# 5_LCD.net
KiCad netlist of a schematic drawn in Altium Designer
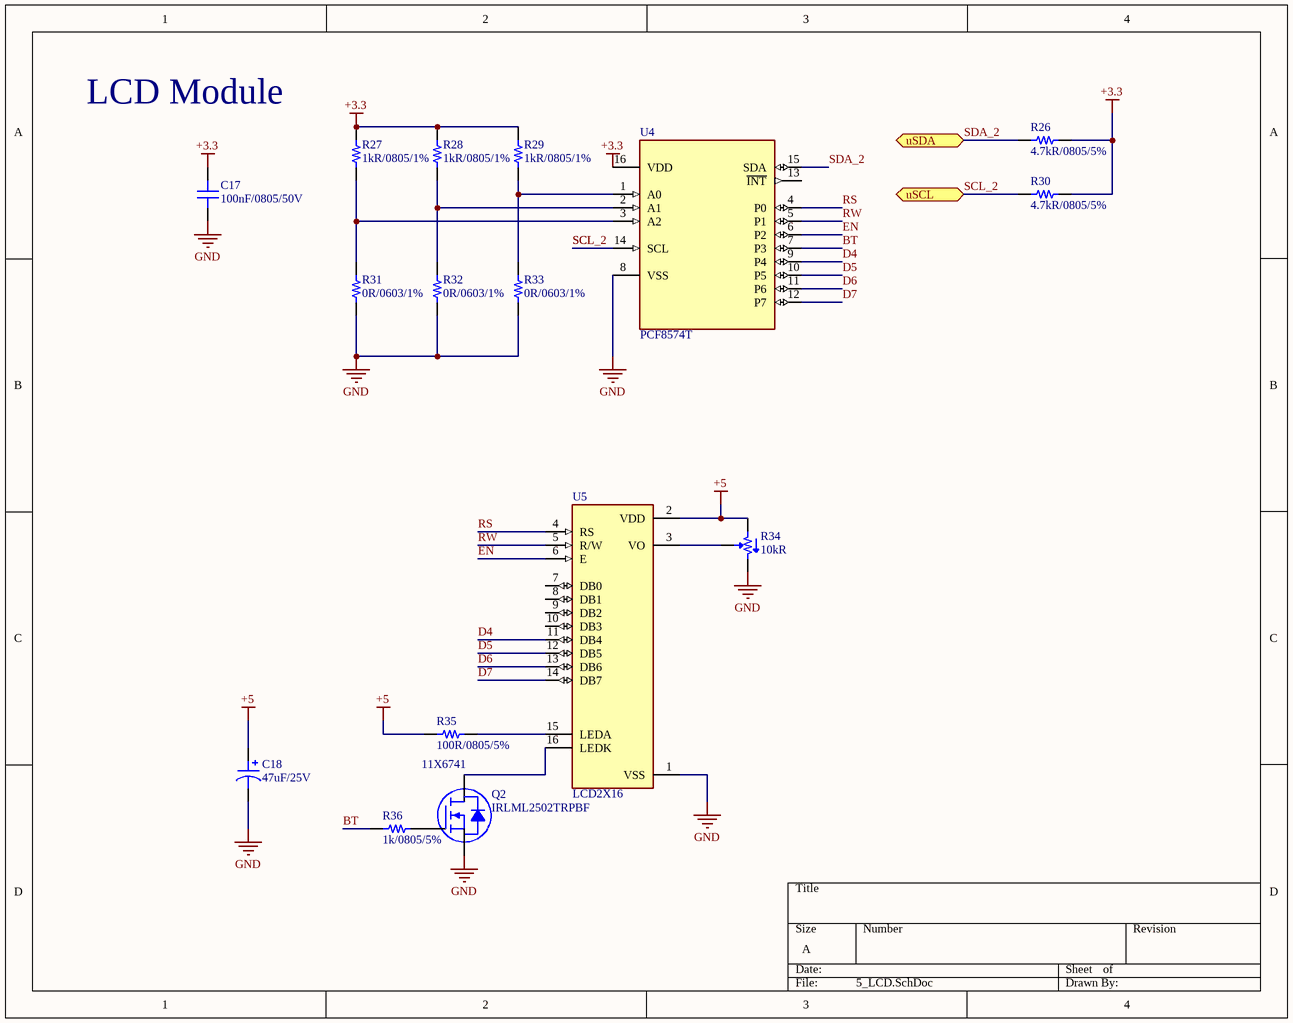
[diagram p0: 5_LCD.SchDoc]

(export (version "E")
  (design (tool "Eeschema 10.0.6"))
  (components
    (comp (ref "C17")
      (value "100nF/0805/50V")
      (footprint "CAP FILM 0805")
      (description "Multilayer Ceramic Capacitor, 0.1 uF, 50 V, ï¿½ 10%, X7R, 0805 [2012 Metric]")
      (fields
        (field (name "MANUFACTURER") "Samsung")
        (field (name "MANUFACTURER PART NUMBER") "CL21B104KBCNNNC")
      )
      (libsource (lib "NLOC_Altium_Library") (part "Capacitor - MLCC"))
    )
    (comp (ref "C18")
      (value "47uF/25V")
      (footprint "CAP ALSMD 6.6MM H5.4MM")
      (description "SMT Polarised Capacitor")
      (libsource (lib "NLOC_Altium_Library") (part "Capacitor - Aluminum"))
    )
    (comp (ref "Q2")
      (value "IRLML2502TRPBF")
      (footprint "TI SOT-23-3 DBZ")
      (description "Mosfet, Power; N-ch; Vdss 20V; Rds(on) 0.035 Ohm; Id 4.2A; MICRO3; Pd 1.25W; Vgs +/-12V")
      (fields
        (field (name "SUPPLIER PART NUMBER 1") "11X6741")
        (field (name "MANUFACTURER") "International Rectifier")
      )
      (libsource (lib "NLOC_Sche") (part "MOSFET N-CH"))
    )
    (comp (ref "R26")
      (value "4.7kR/0805/5%")
      (footprint "RES 0805_2012")
      (description "SMD Chip Resistor, 4.7 kOhm, ± 5%, 125 mW, 0805 [2012 Metric], Thick Film, General Purpose")
      (fields
        (field (name "MANUFACTURER") "Vishay Dale")
        (field (name "MANUFACTURER PART NUMBER") "CRCW08054K70JNEA")
      )
      (libsource (lib "NLOC_Altium_Library") (part "Resistor"))
    )
    (comp (ref "R27")
      (value "1kR/0805/1%")
      (footprint "RES 0805_2012")
      (description "SMD Chip Resistor, 1 kOhm, ï¿½ 1%, 125 mW, 0805 [2012 Metric], Thick Film, General Purpose")
      (fields
        (field (name "MANUFACTURER") "Yageo")
        (field (name "MANUFACTURER PART NUMBER") "RC0805FR-071KL")
      )
      (libsource (lib "NLOC_Altium_Library") (part "Resistor"))
    )
    (comp (ref "R28")
      (value "1kR/0805/1%")
      (footprint "RES 0805_2012")
      (description "SMD Chip Resistor, 1 kOhm, ï¿½ 1%, 125 mW, 0805 [2012 Metric], Thick Film, General Purpose")
      (fields
        (field (name "MANUFACTURER") "Yageo")
        (field (name "MANUFACTURER PART NUMBER") "RC0805FR-071KL")
      )
      (libsource (lib "NLOC_Altium_Library") (part "Resistor"))
    )
    (comp (ref "R29")
      (value "1kR/0805/1%")
      (footprint "RES 0805_2012")
      (description "SMD Chip Resistor, 1 kOhm, ï¿½ 1%, 125 mW, 0805 [2012 Metric], Thick Film, General Purpose")
      (fields
        (field (name "MANUFACTURER") "Yageo")
        (field (name "MANUFACTURER PART NUMBER") "RC0805FR-071KL")
      )
      (libsource (lib "NLOC_Altium_Library") (part "Resistor"))
    )
    (comp (ref "R30")
      (value "4.7kR/0805/5%")
      (footprint "RES 0805_2012")
      (description "SMD Chip Resistor, 4.7 kOhm, ± 5%, 125 mW, 0805 [2012 Metric], Thick Film, General Purpose")
      (fields
        (field (name "MANUFACTURER") "Vishay Dale")
        (field (name "MANUFACTURER PART NUMBER") "CRCW08054K70JNEA")
      )
      (libsource (lib "NLOC_Altium_Library") (part "Resistor"))
    )
    (comp (ref "R31")
      (value "0R/0603/1%")
      (footprint "RES 0603_1608")
      (description "SMD Chip Resistor, 1 kOhm, ï¿½ 1%, 125 mW, 0805 [2012 Metric], Thick Film, General Purpose")
      (fields
        (field (name "MANUFACTURER") "Yageo")
        (field (name "MANUFACTURER PART NUMBER") "RC0805FR-071KL")
      )
      (libsource (lib "NLOC_Altium_Library") (part "Resistor"))
    )
    (comp (ref "R32")
      (value "0R/0603/1%")
      (footprint "RES 0603_1608")
      (description "SMD Chip Resistor, 1 kOhm, ï¿½ 1%, 125 mW, 0805 [2012 Metric], Thick Film, General Purpose")
      (fields
        (field (name "MANUFACTURER") "Yageo")
        (field (name "MANUFACTURER PART NUMBER") "RC0805FR-071KL")
      )
      (libsource (lib "NLOC_Altium_Library") (part "Resistor"))
    )
    (comp (ref "R33")
      (value "0R/0603/1%")
      (footprint "RES 0603_1608")
      (description "SMD Chip Resistor, 1 kOhm, ï¿½ 1%, 125 mW, 0805 [2012 Metric], Thick Film, General Purpose")
      (fields
        (field (name "MANUFACTURER") "Yageo")
        (field (name "MANUFACTURER PART NUMBER") "RC0805FR-071KL")
      )
      (libsource (lib "NLOC_Altium_Library") (part "Resistor"))
    )
    (comp (ref "R34")
      (value "10kR")
      (footprint "POT Panasonic EVM")
      (description "Res Cermet Trimmer 10K Ohm 25% 3/20W 1Turn Foot Print SMD Carrier T/R")
      (fields
        (field (name "MANUFACTURER") "Panasonic")
        (field (name "MANUFACTURER PART NUMBER") "EVM-2WSX80B14")
      )
      (libsource (lib "NLOC_Altium_Library") (part "Potentiometer"))
    )
    (comp (ref "R35")
      (value "100R/0805/5%")
      (footprint "RES 0805_2012")
      (description "SMD Chip Resistor, 100 Ohm, ± 5%, 125 mW, 0805 [2012 Metric], Thick Film, General Purpose")
      (fields
        (field (name "MANUFACTURER") "Yageo")
        (field (name "MANUFACTURER PART NUMBER") "AC0805JR-07100RL")
      )
      (libsource (lib "NLOC_Altium_Library") (part "Resistor"))
    )
    (comp (ref "R36")
      (value "1k/0805/5%")
      (footprint "RES 0805_2012")
      (description "Res Thin Film 0805 2K Ohm 0.1% 0.125W(1/8W) ±25ppm/C Pad SMD T/R")
      (fields
        (field (name "MANUFACTURER") "Yageo")
        (field (name "MANUFACTURER PART NUMBER") "RT0805BRD072KL")
      )
      (libsource (lib "NLOC_Altium_Library") (part "Resistor"))
    )
    (comp (ref "U4")
      (value "PCF8574T")
      (footprint "SOIC127P1032X265-16N")
      (description "I/O Expander 8 IÂ²C 100 kHz 20-SSOP")
      (fields (field (name "MF") "NXP Semiconductors"))
      (libsource (lib "PCF8574T") (part "PCF8574T"))
    )
    (comp (ref "U5")
      (value "LCD2X16")
      (footprint "LCD_LCD2X16")
      (description "Display; Display: LCD 2x16 characters (blue backlight)")
      (libsource (lib "LCD2X16") (part "LCD2X16"))
    )
  )
  (nets
    (net (code "1") (name "+3.3") (class "Default")
      (node (ref "C17") (pin "2") (pinfunction "2_2") (pintype "passive"))
      (node (ref "R26") (pin "2") (pinfunction "2_2") (pintype "passive"))
      (node (ref "R27") (pin "2") (pinfunction "2_2") (pintype "passive"))
      (node (ref "R28") (pin "2") (pinfunction "2_2") (pintype "passive"))
      (node (ref "R29") (pin "2") (pinfunction "2_2") (pintype "passive"))
      (node (ref "R30") (pin "2") (pinfunction "2_2") (pintype "passive"))
      (node (ref "U4") (pin "16") (pinfunction "VDD_16") (pintype "power_in"))
    )
    (net (code "2") (name "+5") (class "Default")
      (node (ref "C18") (pin "1") (pinfunction "1_1") (pintype "passive"))
      (node (ref "R34") (pin "1") (pinfunction "1_1") (pintype "passive"))
      (node (ref "R35") (pin "1") (pinfunction "1_1") (pintype "passive"))
      (node (ref "U5") (pin "2") (pinfunction "VDD_2") (pintype "power_in"))
    )
    (net (code "3") (name "/BT") (class "Default")
      (node (ref "R36") (pin "2") (pinfunction "2_2") (pintype "passive"))
      (node (ref "U4") (pin "7") (pinfunction "P3_7") (pintype "bidirectional"))
    )
    (net (code "4") (name "/D4") (class "Default")
      (node (ref "U4") (pin "9") (pinfunction "P4_9") (pintype "bidirectional"))
      (node (ref "U5") (pin "11") (pinfunction "DB4_11") (pintype "bidirectional"))
    )
    (net (code "5") (name "/D5") (class "Default")
      (node (ref "U4") (pin "10") (pinfunction "P5_10") (pintype "bidirectional"))
      (node (ref "U5") (pin "12") (pinfunction "DB5_12") (pintype "bidirectional"))
    )
    (net (code "6") (name "/D6") (class "Default")
      (node (ref "U4") (pin "11") (pinfunction "P6_11") (pintype "bidirectional"))
      (node (ref "U5") (pin "13") (pinfunction "DB6_13") (pintype "bidirectional"))
    )
    (net (code "7") (name "/D7") (class "Default")
      (node (ref "U4") (pin "12") (pinfunction "P7_12") (pintype "bidirectional"))
      (node (ref "U5") (pin "14") (pinfunction "DB7_14") (pintype "bidirectional"))
    )
    (net (code "8") (name "/EN") (class "Default")
      (node (ref "U4") (pin "6") (pinfunction "P2_6") (pintype "bidirectional"))
      (node (ref "U5") (pin "6") (pinfunction "E_6") (pintype "input"))
    )
    (net (code "9") (name "/RS") (class "Default")
      (node (ref "U4") (pin "4") (pinfunction "P0_4") (pintype "bidirectional"))
      (node (ref "U5") (pin "4") (pinfunction "RS_4") (pintype "input"))
    )
    (net (code "10") (name "/RW") (class "Default")
      (node (ref "U4") (pin "5") (pinfunction "P1_5") (pintype "bidirectional"))
      (node (ref "U5") (pin "5") (pinfunction "R/W_5") (pintype "input"))
    )
    (net (code "11") (name "/SCL") (class "Default")
      (node (ref "R30") (pin "1") (pinfunction "1_1") (pintype "passive"))
      (node (ref "U4") (pin "14") (pinfunction "SCL_14") (pintype "input"))
    )
    (net (code "12") (name "/SDA_2") (class "Default")
      (node (ref "R26") (pin "1") (pinfunction "1_1") (pintype "passive"))
      (node (ref "U4") (pin "15") (pinfunction "SDA_15") (pintype "bidirectional"))
    )
    (net (code "13") (name "GND") (class "Default")
      (node (ref "C17") (pin "1") (pinfunction "1_1") (pintype "passive"))
      (node (ref "C18") (pin "2") (pinfunction "2_2") (pintype "passive"))
      (node (ref "Q2") (pin "2") (pinfunction "S_2") (pintype "passive"))
      (node (ref "R31") (pin "1") (pinfunction "1_1") (pintype "passive"))
      (node (ref "R32") (pin "1") (pinfunction "1_1") (pintype "passive"))
      (node (ref "R33") (pin "1") (pinfunction "1_1") (pintype "passive"))
      (node (ref "R34") (pin "3") (pinfunction "3_3") (pintype "passive"))
      (node (ref "U4") (pin "8") (pinfunction "VSS_8") (pintype "passive"))
      (node (ref "U5") (pin "1") (pinfunction "VSS_1") (pintype "power_in"))
    )
    (net (code "14") (name "Net-(Q2-D)") (class "Default")
      (node (ref "Q2") (pin "3") (pinfunction "D_3") (pintype "passive"))
      (node (ref "U5") (pin "16") (pinfunction "LEDK_16") (pintype "passive"))
    )
    (net (code "15") (name "Net-(Q2-G)") (class "Default")
      (node (ref "Q2") (pin "1") (pinfunction "G_1") (pintype "passive"))
      (node (ref "R36") (pin "1") (pinfunction "1_1") (pintype "passive"))
    )
    (net (code "16") (name "Net-(U4-A0)") (class "Default")
      (node (ref "R29") (pin "1") (pinfunction "1_1") (pintype "passive"))
      (node (ref "R33") (pin "2") (pinfunction "2_2") (pintype "passive"))
      (node (ref "U4") (pin "1") (pinfunction "A0_1") (pintype "input"))
    )
    (net (code "17") (name "Net-(U4-A1)") (class "Default")
      (node (ref "R28") (pin "1") (pinfunction "1_1") (pintype "passive"))
      (node (ref "R32") (pin "2") (pinfunction "2_2") (pintype "passive"))
      (node (ref "U4") (pin "2") (pinfunction "A1_2") (pintype "input"))
    )
    (net (code "18") (name "Net-(U4-A2)") (class "Default")
      (node (ref "R27") (pin "1") (pinfunction "1_1") (pintype "passive"))
      (node (ref "R31") (pin "2") (pinfunction "2_2") (pintype "passive"))
      (node (ref "U4") (pin "3") (pinfunction "A2_3") (pintype "input"))
    )
    (net (code "19") (name "Net-(U5-LEDA)") (class "Default")
      (node (ref "R35") (pin "2") (pinfunction "2_2") (pintype "passive"))
      (node (ref "U5") (pin "15") (pinfunction "LEDA_15") (pintype "passive"))
    )
    (net (code "20") (name "Net-(U5-VO)") (class "Default")
      (node (ref "R34") (pin "2") (pinfunction "2_2") (pintype "passive"))
      (node (ref "U5") (pin "3") (pinfunction "VO_3") (pintype "passive"))
    )
    (net (code "21") (name "unconnected-(U4-~{INT}-Pad13)") (class "Default")
      (node (ref "U4") (pin "13") (pinfunction "~{INT}_13") (pintype "output"))
    )
    (net (code "22") (name "unconnected-(U5-DB0-Pad7)") (class "Default")
      (node (ref "U5") (pin "7") (pinfunction "DB0_7") (pintype "bidirectional"))
    )
    (net (code "23") (name "unconnected-(U5-DB1-Pad8)") (class "Default")
      (node (ref "U5") (pin "8") (pinfunction "DB1_8") (pintype "bidirectional"))
    )
    (net (code "24") (name "unconnected-(U5-DB2-Pad9)") (class "Default")
      (node (ref "U5") (pin "9") (pinfunction "DB2_9") (pintype "bidirectional"))
    )
    (net (code "25") (name "unconnected-(U5-DB3-Pad10)") (class "Default")
      (node (ref "U5") (pin "10") (pinfunction "DB3_10") (pintype "bidirectional"))
    )
  )
)
